# Perf.net
KiCad netlist of a schematic drawn in Altium Designer
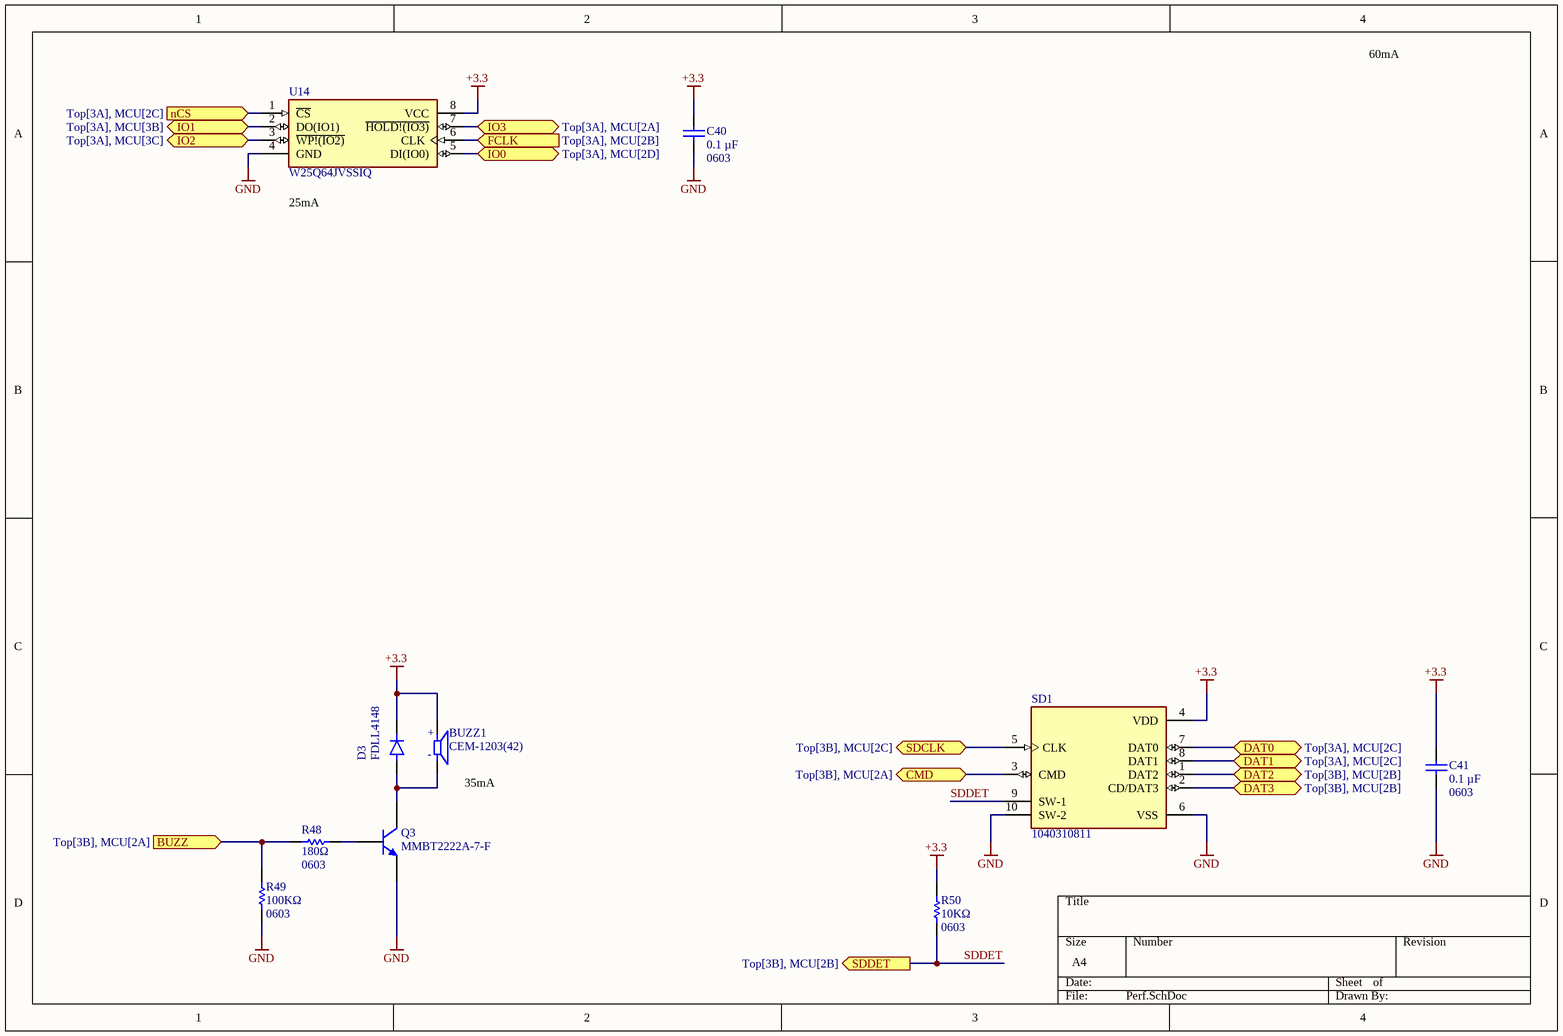
[diagram p0: Perf.SchDoc]

(export (version "E")
  (design (tool "Eeschema 10.0.6"))
  (components
    (comp (ref "BUZZ1")
      (value "CEM-1203(42)")
      (footprint "Through Hole 12mm")
      (fields (field (name "VOLTAGE") "3.5V"))
      (libsource (lib "Same Sky") (part "CEM-1203(42)"))
    )
    (comp (ref "C40")
      (value "0.1 µF")
      (footprint "0603")
      (description "0.1 µF ±20% 100V Ceramic Capacitor X7R 0603 (1608 Metric)")
      (fields (field (name "CASE") "0603") (field (name "TOLERANCE") "±20%") (field (name "VOLTAGE") "100V"))
      (libsource (lib "Murata Electronics") (part "GRM188R72A104MA35J"))
    )
    (comp (ref "C41")
      (value "0.1 µF")
      (footprint "0603")
      (description "0.1 µF ±20% 100V Ceramic Capacitor X7R 0603 (1608 Metric)")
      (fields (field (name "CASE") "0603") (field (name "TOLERANCE") "±20%") (field (name "VOLTAGE") "100V"))
      (libsource (lib "Murata Electronics") (part "GRM188R72A104MA35J"))
    )
    (comp (ref "D3")
      (value "FDLL4148")
      (footprint "SOD80")
      (description "Diode 100 V 200mA Surface Mount SOD-80")
      (libsource (lib "Onsemi") (part "FDLL4148"))
    )
    (comp (ref "Q3")
      (value "MMBT2222A-7-F")
      (footprint "SOT-23-3")
      (description "Bipolar (BJT) Transistor NPN 40 V 600 mA 300MHz 310 mW Surface Mount SOT-23-3")
      (libsource (lib "Diodes Incorporated") (part "MMBT2222A-7-F"))
    )
    (comp (ref "R48")
      (value "180Ω")
      (footprint "0603")
      (description "180 Ohms ±1% 0.1W, 1/10W Chip Resistor 0603 (1608 Metric) Automotive AEC-Q200 Thick Film")
      (fields (field (name "CASE") "0603") (field (name "TOLERANCE") "1%") (field (name "POWER") "0.1W"))
      (libsource (lib "Stackpole Electronics Inc") (part "RMCF0603FT180R"))
    )
    (comp (ref "R49")
      (value "100KΩ")
      (footprint "0603")
      (description "100 kOhms ±1% 0.1W, 1/10W Chip Resistor 0603 (1608 Metric) Automotive AEC-Q200 Thick Film")
      (fields (field (name "CASE") "0603") (field (name "TOLERANCE") "1%") (field (name "POWER") "0.1W"))
      (libsource (lib "Stackpole Electronics Inc") (part "RMCF0603FG100K"))
    )
    (comp (ref "R50")
      (value "10KΩ")
      (footprint "0603")
      (description "10 kOhms ±1% 0.1W, 1/10W Chip Resistor 0603 (1608 Metric) Automotive AEC-Q200 Thick Film")
      (fields (field (name "CASE") "0603") (field (name "TOLERANCE") "1%") (field (name "POWER") "0.1W"))
      (libsource (lib "Stackpole Electronics Inc") (part "RMCF0603FG10K0"))
    )
    (comp (ref "SD1")
      (value "1040310811")
      (footprint "PCBComponent_1")
      (description "10 (8 + 2) Position Card Connector Secure Digital - microSD™ Surface Mount, Right Angle Gold")
      (libsource (lib "Molex") (part "1040310811"))
    )
    (comp (ref "U14")
      (value "W25Q64JVSSIQ")
      (footprint "8-SOIC")
      (description "FLASH - NOR Memory IC 64Mbit SPI - Quad I/O 133 MHz 8-SOIC")
      (libsource (lib "Winbond Electronics") (part "W25Q64JVSSIQ"))
    )
  )
  (nets
    (net (code "1") (name "+3.3") (class "Default")
      (node (ref "BUZZ1") (pin "P") (pinfunction "P_P") (pintype "passive"))
      (node (ref "C40") (pin "1") (pinfunction "1_1") (pintype "passive"))
      (node (ref "C41") (pin "1") (pinfunction "1_1") (pintype "passive"))
      (node (ref "D3") (pin "C") (pinfunction "C_C") (pintype "passive"))
      (node (ref "R50") (pin "2") (pinfunction "2_2") (pintype "passive"))
      (node (ref "SD1") (pin "4") (pinfunction "VDD_4") (pintype "power_in"))
      (node (ref "U14") (pin "8") (pinfunction "VCC_8") (pintype "power_in"))
    )
    (net (code "2") (name "/BUZZ") (class "Default")
      (node (ref "R48") (pin "2") (pinfunction "2_2") (pintype "passive"))
      (node (ref "R49") (pin "1") (pinfunction "1_1") (pintype "passive"))
    )
    (net (code "3") (name "/CMD") (class "Default")
      (node (ref "SD1") (pin "3") (pinfunction "CMD_3") (pintype "bidirectional"))
    )
    (net (code "4") (name "/DAT0") (class "Default")
      (node (ref "SD1") (pin "7") (pinfunction "DAT0_7") (pintype "bidirectional"))
    )
    (net (code "5") (name "/DAT1") (class "Default")
      (node (ref "SD1") (pin "8") (pinfunction "DAT1_8") (pintype "bidirectional"))
    )
    (net (code "6") (name "/DAT2") (class "Default")
      (node (ref "SD1") (pin "1") (pinfunction "DAT2_1") (pintype "bidirectional"))
    )
    (net (code "7") (name "/DAT3") (class "Default")
      (node (ref "SD1") (pin "2") (pinfunction "CD/DAT3_2") (pintype "bidirectional"))
    )
    (net (code "8") (name "/FCLK") (class "Default")
      (node (ref "U14") (pin "6") (pinfunction "CLK_6") (pintype "input"))
    )
    (net (code "9") (name "/IO0") (class "Default")
      (node (ref "U14") (pin "5") (pinfunction "DI(IO0)_5") (pintype "bidirectional"))
    )
    (net (code "10") (name "/IO1") (class "Default")
      (node (ref "U14") (pin "2") (pinfunction "DO(IO1)_2") (pintype "bidirectional"))
    )
    (net (code "11") (name "/IO2") (class "Default")
      (node (ref "U14") (pin "3") (pinfunction "~{WP!(IO2)}_3") (pintype "bidirectional"))
    )
    (net (code "12") (name "/IO3") (class "Default")
      (node (ref "U14") (pin "7") (pinfunction "~{HOLD!(IO3)}_7") (pintype "bidirectional"))
    )
    (net (code "13") (name "/SDCLK") (class "Default")
      (node (ref "SD1") (pin "5") (pinfunction "CLK_5") (pintype "input"))
    )
    (net (code "14") (name "/SDDET") (class "Default")
      (node (ref "R50") (pin "1") (pinfunction "1_1") (pintype "passive"))
      (node (ref "SD1") (pin "9") (pinfunction "SW-1_9") (pintype "passive"))
    )
    (net (code "15") (name "/nCS") (class "Default")
      (node (ref "U14") (pin "1") (pinfunction "~{CS}_1") (pintype "input"))
    )
    (net (code "16") (name "GND") (class "Default")
      (node (ref "C40") (pin "2") (pinfunction "2_2") (pintype "passive"))
      (node (ref "C41") (pin "2") (pinfunction "2_2") (pintype "passive"))
      (node (ref "Q3") (pin "2") (pinfunction "E_2") (pintype "passive"))
      (node (ref "R49") (pin "2") (pinfunction "2_2") (pintype "passive"))
      (node (ref "SD1") (pin "10") (pinfunction "SW-2_10") (pintype "passive"))
      (node (ref "SD1") (pin "6") (pinfunction "VSS_6") (pintype "power_in"))
      (node (ref "U14") (pin "4") (pinfunction "GND_4") (pintype "power_in"))
    )
    (net (code "17") (name "Net-(Q3-B)") (class "Default")
      (node (ref "Q3") (pin "1") (pinfunction "B_1") (pintype "passive"))
      (node (ref "R48") (pin "1") (pinfunction "1_1") (pintype "passive"))
    )
    (net (code "18") (name "Net-(Q3-C)") (class "Default")
      (node (ref "BUZZ1") (pin "N") (pinfunction "N_N") (pintype "passive"))
      (node (ref "D3") (pin "A") (pinfunction "A_A") (pintype "passive"))
      (node (ref "Q3") (pin "3") (pinfunction "C_3") (pintype "passive"))
    )
  )
)
